# LV_power.net
KiCad netlist of a schematic drawn in Altium Designer
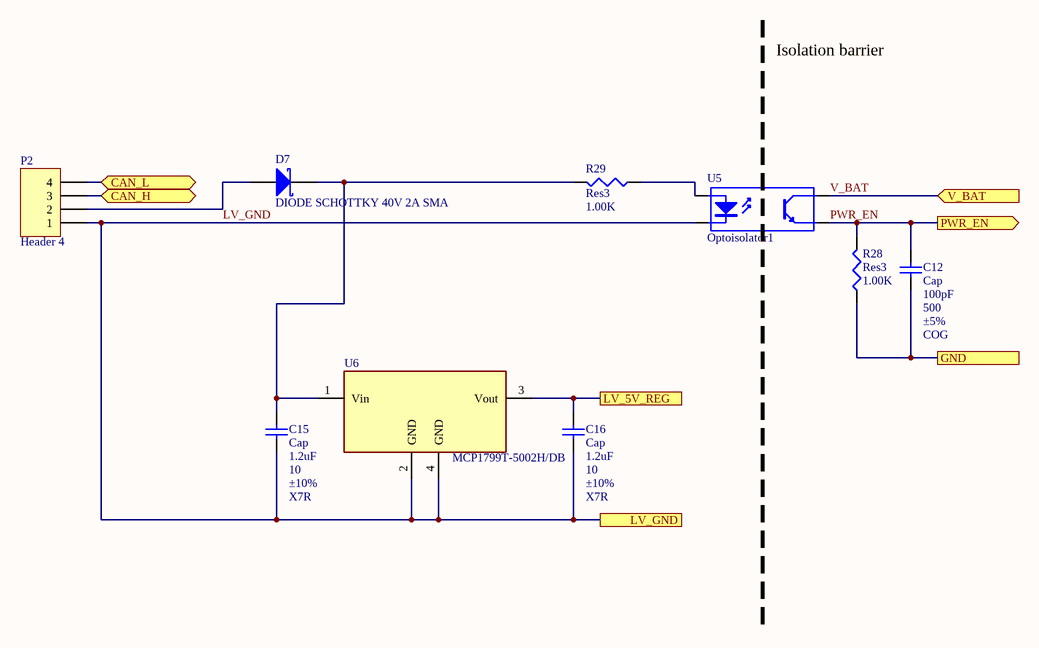
[diagram p0: LV_power.SchDoc]

(export (version "E")
  (design (tool "Eeschema 10.0.6"))
  (components
    (comp (ref "C12")
      (value "Cap")
      (footprint "CAPC2012X09M")
      (description "CAP CER 100pF 500v COG 0805")
      (fields
        (field (name "ALTIUM_VALUE") "100pF")
        (field (name "WV") "500")
        (field (name "TOLERANCE") "±5%")
        (field (name "TYPE") "COG")
        (field (name "MPN") "C0805C101JCGACTU")
      )
      (libsource (lib "esd_library") (part "CAP-COG-100pF-500V-±5%"))
    )
    (comp (ref "C15")
      (value "Cap")
      (footprint "CAPC2012X09M")
      (description "CAP CER 1.2uF 10v X7R 0805")
      (fields
        (field (name "ALTIUM_VALUE") "1.2uF")
        (field (name "WV") "10")
        (field (name "TOLERANCE") "±10%")
        (field (name "TYPE") "X7R")
        (field (name "MPN") "C0805C125K8RACTU")
      )
      (libsource (lib "esd_library") (part "CAP-X7R-1.2uF-10V-±10%"))
    )
    (comp (ref "C16")
      (value "Cap")
      (footprint "CAPC2012X09M")
      (description "CAP CER 1.2uF 10v X7R 0805")
      (fields
        (field (name "ALTIUM_VALUE") "1.2uF")
        (field (name "WV") "10")
        (field (name "TOLERANCE") "±10%")
        (field (name "TYPE") "X7R")
        (field (name "MPN") "C0805C125K8RACTU")
      )
      (libsource (lib "esd_library") (part "CAP-X7R-1.2uF-10V-±10%"))
    )
    (comp (ref "D7")
      (value "DIODE SCHOTTKY 40V 2A SMA")
      (footprint "DIOM4326X23M")
      (description "Schottky Rectifier")
      (fields (field (name "MPN") "B240A-13-F"))
      (libsource (lib "esd_library") (part "DIODE SCHOTTKY 40V 2A SMA"))
    )
    (comp (ref "P2")
      (value "Header 4")
      (footprint "HDR1X4")
      (description "Header, 4-Pin")
      (fields (field (name "PUBLISHER") "Altium Limited"))
      (libsource (lib "Miscellaneous Connectors") (part "Header 4"))
    )
    (comp (ref "R28")
      (value "Res3")
      (footprint "RESC2112X05M")
      (description "RES SMD 1.00K OHM 1% 1/8W 0805")
      (fields (field (name "ALTIUM_VALUE") "1.00K") (field (name "MPN") "CRCW08051K00FKEA"))
      (libsource (lib "esd_library") (part "Resistor_1.00K"))
    )
    (comp (ref "R29")
      (value "Res3")
      (footprint "RESC2112X05M")
      (description "RES SMD 1.00K OHM 1% 1/8W 0805")
      (fields (field (name "ALTIUM_VALUE") "1.00K") (field (name "MPN") "CRCW08051K00FKEA"))
      (libsource (lib "esd_library") (part "Resistor_1.00K"))
    )
    (comp (ref "U5")
      (value "Optoisolator1")
      (footprint "DIP-4")
      (description "4-Pin Phototransistor Optocoupler")
      (fields (field (name "PUBLISHER") "Altium Limited"))
      (libsource (lib "Miscellaneous Devices") (part "Optoisolator1"))
    )
    (comp (ref "U6")
      (value "MCP1799T-5002H/DB")
      (footprint "SOT223")
      (description "LDO 5V 80mA SOT-223")
      (fields (field (name "MF") "Texas Instruments") (field (name "MP") "LM1117IMP-5.0"))
      (libsource (lib "MCP1799T-5002HDB") (part "LM1117IMP-5.0"))
    )
  )
  (nets
    (net (code "1") (name "/CAN_H") (class "Default")
      (node (ref "P2") (pin "3") (pinfunction "3_3") (pintype "passive"))
    )
    (net (code "2") (name "/CAN_L") (class "Default")
      (node (ref "P2") (pin "4") (pinfunction "4_4") (pintype "passive"))
    )
    (net (code "3") (name "/GND") (class "Default")
      (node (ref "C12") (pin "1") (pinfunction "1_1") (pintype "passive"))
      (node (ref "R28") (pin "1") (pinfunction "1_1") (pintype "passive"))
    )
    (net (code "4") (name "/LV_5V_REG") (class "Default")
      (node (ref "C16") (pin "2") (pinfunction "2_2") (pintype "passive"))
      (node (ref "U6") (pin "3") (pinfunction "Vout_3") (pintype "power_in"))
    )
    (net (code "5") (name "/LV_GND") (class "Default")
      (node (ref "C15") (pin "1") (pinfunction "1_1") (pintype "passive"))
      (node (ref "C16") (pin "1") (pinfunction "1_1") (pintype "passive"))
      (node (ref "P2") (pin "1") (pinfunction "1_1") (pintype "passive"))
      (node (ref "U5") (pin "2") (pinfunction "K_2") (pintype "passive"))
      (node (ref "U6") (pin "2") (pinfunction "GND_2") (pintype "power_in"))
      (node (ref "U6") (pin "4") (pinfunction "GND_4") (pintype "power_in"))
    )
    (net (code "6") (name "/PWR_EN") (class "Default")
      (node (ref "C12") (pin "2") (pinfunction "2_2") (pintype "passive"))
      (node (ref "R28") (pin "2") (pinfunction "2_2") (pintype "passive"))
      (node (ref "U5") (pin "3") (pinfunction "E_3") (pintype "passive"))
    )
    (net (code "7") (name "/V_BAT") (class "Default")
      (node (ref "U5") (pin "4") (pinfunction "C_4") (pintype "passive"))
    )
    (net (code "8") (name "Net-(D7-A)") (class "Default")
      (node (ref "D7") (pin "2") (pinfunction "A_2") (pintype "passive"))
      (node (ref "P2") (pin "2") (pinfunction "2_2") (pintype "passive"))
    )
    (net (code "9") (name "Net-(D7-K)") (class "Default")
      (node (ref "C15") (pin "2") (pinfunction "2_2") (pintype "passive"))
      (node (ref "D7") (pin "1") (pinfunction "K_1") (pintype "passive"))
      (node (ref "R29") (pin "2") (pinfunction "2_2") (pintype "passive"))
      (node (ref "U6") (pin "1") (pinfunction "Vin_1") (pintype "power_in"))
    )
    (net (code "10") (name "Net-(U5-A)") (class "Default")
      (node (ref "R29") (pin "1") (pinfunction "1_1") (pintype "passive"))
      (node (ref "U5") (pin "1") (pinfunction "A_1") (pintype "passive"))
    )
  )
)
